# Sum-Comp.net
KiCad netlist of a schematic drawn in Altium Designer
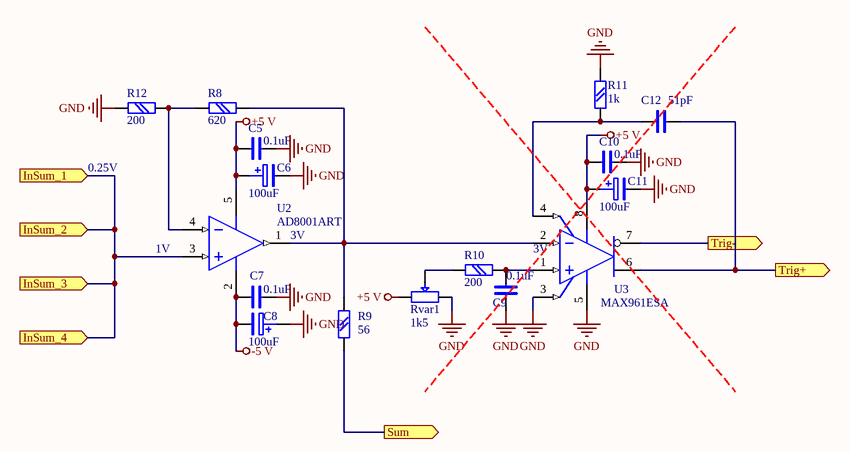
[diagram p0: Sum-Comp.SchDoc]

(export (version "E")
  (design (tool "Eeschema 10.0.6"))
  (components
    (comp (ref "C5") (value "0.1uF") (footprint "chip0805") (libsource (lib "vDevice") (part "C")))
    (comp (ref "C6") (value "100uF") (footprint "CEL-SMD300") (libsource (lib "vDevice") (part "C POL")))
    (comp (ref "C7") (value "0.1uF") (footprint "chip0805") (libsource (lib "vDevice") (part "C")))
    (comp (ref "C8") (value "100uF") (footprint "CEL-SMD300") (libsource (lib "vDevice") (part "C POL")))
    (comp (ref "C9") (value "0.1uF") (footprint "chip0805") (libsource (lib "vDevice") (part "C")))
    (comp (ref "C10") (value "0.1uF") (footprint "chip0805") (libsource (lib "vDevice") (part "C")))
    (comp (ref "C11") (value "100uF") (footprint "CEL-SMD300") (libsource (lib "vDevice") (part "C POL")))
    (comp (ref "C12") (value "51pF") (footprint "chip0805") (libsource (lib "vDevice") (part "C")))
    (comp (ref "R8") (value "620") (footprint "chip0805") (libsource (lib "vDevice") (part "R")))
    (comp (ref "R9") (value "56") (footprint "chip0805") (libsource (lib "vDevice") (part "R")))
    (comp (ref "R10") (value "200") (footprint "chip0805") (libsource (lib "vDevice") (part "R")))
    (comp (ref "R11") (value "1k") (footprint "chip0805") (libsource (lib "vDevice") (part "R")))
    (comp (ref "R12") (value "200") (footprint "chip0805") (libsource (lib "vDevice") (part "R")))
    (comp (ref "Rvar1") (value "1k5") (footprint "RVAR4") (libsource (lib "vDevice") (part "R VAR")))
    (comp (ref "U2")
      (value "AD8001ART")
      (footprint "RT-5")
      (description "Low Cost, 300MHz Voltage Feedback Amplifier")
      (fields (field (name "PUBLISHER") "Altium Limited"))
      (libsource (lib "AD Operational Amplifier") (part "AD8055ART"))
    )
    (comp (ref "U3")
      (value "MAX961ESA")
      (footprint "NSO8_N")
      (description "Single Ultra-High-Speed, +3V/+5V, Beyond-the-Rails Comparator")
      (fields (field (name "PUBLISHER") "Altium Limited"))
      (libsource (lib "Maxim Analog Comparator") (part "MAX961ESA"))
    )
  )
  (nets
    (net (code "1") (name "+5 V") (class "Default")
      (node (ref "C10") (pin "2") (pinfunction "2_2") (pintype "passive"))
      (node (ref "C11") (pin "+") (pinfunction "+_+") (pintype "passive"))
      (node (ref "C5") (pin "2") (pinfunction "2_2") (pintype "passive"))
      (node (ref "C6") (pin "+") (pinfunction "+_+") (pintype "passive"))
      (node (ref "Rvar1") (pin "1") (pinfunction "1_1") (pintype "passive"))
      (node (ref "U2") (pin "5") (pinfunction "V+_5") (pintype "power_in"))
      (node (ref "U3") (pin "8") (pinfunction "V+_8") (pintype "power_in"))
    )
    (net (code "2") (name "-5 V") (class "Default")
      (node (ref "C7") (pin "2") (pinfunction "2_2") (pintype "passive"))
      (node (ref "C8") (pin "-") (pinfunction "-_-") (pintype "passive"))
      (node (ref "U2") (pin "2") (pinfunction "V-_2") (pintype "power_in"))
    )
    (net (code "3") (name "/InSum_1") (class "Default")
      (node (ref "U2") (pin "3") (pinfunction "IN+_3") (pintype "input"))
    )
    (net (code "4") (name "/Sum") (class "Default")
      (node (ref "R9") (pin "1") (pinfunction "1_1") (pintype "passive"))
    )
    (net (code "5") (name "/Trig+") (class "Default")
      (node (ref "C12") (pin "2") (pinfunction "2_2") (pintype "passive"))
      (node (ref "U3") (pin "6") (pinfunction "Q_6") (pintype "tri_state"))
    )
    (net (code "6") (name "/Trig-") (class "Default")
      (node (ref "U3") (pin "7") (pinfunction "~{Q}_7") (pintype "tri_state"))
    )
    (net (code "7") (name "GND") (class "Default")
      (node (ref "C10") (pin "1") (pinfunction "1_1") (pintype "passive"))
      (node (ref "C11") (pin "-") (pinfunction "-_-") (pintype "passive"))
      (node (ref "C5") (pin "1") (pinfunction "1_1") (pintype "passive"))
      (node (ref "C6") (pin "-") (pinfunction "-_-") (pintype "passive"))
      (node (ref "C7") (pin "1") (pinfunction "1_1") (pintype "passive"))
      (node (ref "C8") (pin "+") (pinfunction "+_+") (pintype "passive"))
      (node (ref "C9") (pin "1") (pinfunction "1_1") (pintype "passive"))
      (node (ref "R11") (pin "2") (pinfunction "2_2") (pintype "passive"))
      (node (ref "R12") (pin "2") (pinfunction "2_2") (pintype "passive"))
      (node (ref "Rvar1") (pin "3") (pinfunction "3_3") (pintype "passive"))
      (node (ref "U3") (pin "3") (pinfunction "SHDN_3") (pintype "input"))
      (node (ref "U3") (pin "5") (pinfunction "GND_5") (pintype "power_in"))
    )
    (net (code "8") (name "Net-(R10-Pad1)") (class "Default")
      (node (ref "R10") (pin "1") (pinfunction "1_1") (pintype "passive"))
      (node (ref "Rvar1") (pin "2") (pinfunction "2_2") (pintype "passive"))
    )
    (net (code "9") (name "Net-(U2-IN-)") (class "Default")
      (node (ref "R12") (pin "1") (pinfunction "1_1") (pintype "passive"))
      (node (ref "R8") (pin "1") (pinfunction "1_1") (pintype "passive"))
      (node (ref "U2") (pin "4") (pinfunction "IN-_4") (pintype "input"))
    )
    (net (code "10") (name "Net-(U2-OUT)") (class "Default")
      (node (ref "R8") (pin "2") (pinfunction "2_2") (pintype "passive"))
      (node (ref "R9") (pin "2") (pinfunction "2_2") (pintype "passive"))
      (node (ref "U2") (pin "1") (pinfunction "OUT_1") (pintype "output"))
      (node (ref "U3") (pin "2") (pinfunction "IN-_2") (pintype "input"))
    )
    (net (code "11") (name "Net-(U3-IN+)") (class "Default")
      (node (ref "C9") (pin "2") (pinfunction "2_2") (pintype "passive"))
      (node (ref "R10") (pin "2") (pinfunction "2_2") (pintype "passive"))
      (node (ref "U3") (pin "1") (pinfunction "IN+_1") (pintype "input"))
    )
    (net (code "12") (name "Net-(U3-LE)") (class "Default")
      (node (ref "C12") (pin "1") (pinfunction "1_1") (pintype "passive"))
      (node (ref "R11") (pin "1") (pinfunction "1_1") (pintype "passive"))
      (node (ref "U3") (pin "4") (pinfunction "LE_4") (pintype "input"))
    )
  )
)
